# rev1.net
KiCad netlist of a schematic drawn in EAGLE
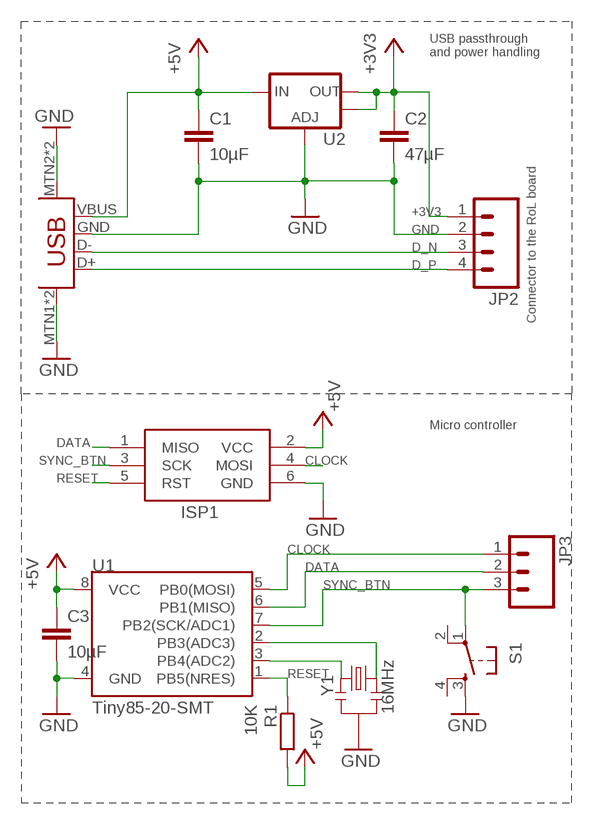
[diagram p0: schematic, sheet 1]

(export (version "E")
  (design (tool "Eeschema 10.0.6"))
  (components
    (comp (ref "C1")
      (value "10µF")
      (footprint "eagle-import:C3216")
      (libsource (lib "eagle-import") (part "C-EUC3216"))
    )
    (comp (ref "C2")
      (value "47µF")
      (footprint "eagle-import:C3216")
      (libsource (lib "eagle-import") (part "C-EUC3216"))
    )
    (comp (ref "C3")
      (value "10µF")
      (footprint "eagle-import:C3216")
      (libsource (lib "eagle-import") (part "C-EUC3216"))
    )
    (comp (ref "ISP1")
      (value "AVRISP-6")
      (footprint "eagle-import:AVRISP")
      (libsource (lib "eagle-import") (part "AVRISP-6"))
    )
    (comp (ref "JP1")
      (value "USBSMD")
      (footprint "eagle-import:USB-MINIB")
      (libsource (lib "eagle-import") (part "USBSMD"))
    )
    (comp (ref "JP2")
      (value "M04LOCK")
      (footprint "eagle-import:1X04_LOCK")
      (libsource (lib "eagle-import") (part "M04LOCK"))
    )
    (comp (ref "JP3")
      (value "M03LOCK")
      (footprint "eagle-import:1X03_LOCK")
      (libsource (lib "eagle-import") (part "M03LOCK"))
    )
    (comp (ref "R1")
      (value "10K")
      (footprint "eagle-import:R0603")
      (libsource (lib "eagle-import") (part "R-EU_R0603"))
    )
    (comp (ref "S1")
      (value "TAC_SWITCHPTH")
      (footprint "eagle-import:TACTILE-PTH")
      (libsource (lib "eagle-import") (part "TAC_SWITCHPTH"))
    )
    (comp (ref "U1")
      (value "Tiny85-20-SMT")
      (footprint "eagle-import:SO08-EIAJ")
      (libsource (lib "eagle-import") (part "ATTINY45TINY85-20-SMT"))
    )
    (comp (ref "U2")
      (value "V_REG_LM1117SOT223")
      (footprint "eagle-import:SOT223")
      (libsource (lib "eagle-import") (part "V_REG_LM1117SOT223"))
    )
    (comp (ref "Y1")
      (value "16MHz")
      (footprint "eagle-import:RESONATOR-SMD")
      (libsource (lib "eagle-import") (part "RESONATORSMD"))
    )
  )
  (nets
    (net (code "1") (name "+3V3") (class "Default")
      (node (ref "C2") (pin "1") (pinfunction "1_1") (pintype "passive"))
      (node (ref "JP2") (pin "1") (pinfunction "1_1") (pintype "passive"))
      (node (ref "U2") (pin "2") (pinfunction "OUT_2") (pintype "output"))
      (node (ref "U2") (pin "4") (pinfunction "OUT_4") (pintype "output"))
    )
    (net (code "2") (name "+5V") (class "Default")
      (node (ref "C1") (pin "1") (pinfunction "1_1") (pintype "passive"))
      (node (ref "C3") (pin "1") (pinfunction "1_1") (pintype "passive"))
      (node (ref "ISP1") (pin "2") (pinfunction "VCC_2") (pintype "power_in"))
      (node (ref "JP1") (pin "VBUS") (pinfunction "VBUS_VBUS") (pintype "bidirectional"))
      (node (ref "R1") (pin "2") (pinfunction "2_2") (pintype "passive"))
      (node (ref "U1") (pin "8") (pinfunction "VCC_8") (pintype "bidirectional"))
      (node (ref "U2") (pin "3") (pinfunction "IN_3") (pintype "input"))
    )
    (net (code "3") (name "/CLOCK") (class "Default")
      (node (ref "ISP1") (pin "4") (pinfunction "MOSI_4") (pintype "output"))
      (node (ref "JP3") (pin "1") (pinfunction "1_1") (pintype "passive"))
      (node (ref "U1") (pin "5") (pinfunction "PB0(MOSI)_5") (pintype "bidirectional"))
    )
    (net (code "4") (name "/DATA") (class "Default")
      (node (ref "ISP1") (pin "1") (pinfunction "MISO_1") (pintype "input"))
      (node (ref "JP3") (pin "2") (pinfunction "2_2") (pintype "passive"))
      (node (ref "U1") (pin "6") (pinfunction "PB1(MISO)_6") (pintype "bidirectional"))
    )
    (net (code "5") (name "/D_N") (class "Default")
      (node (ref "JP1") (pin "D-") (pinfunction "D-_D-") (pintype "bidirectional"))
      (node (ref "JP2") (pin "3") (pinfunction "3_3") (pintype "passive"))
    )
    (net (code "6") (name "/D_P") (class "Default")
      (node (ref "JP1") (pin "D+") (pinfunction "D+_D+") (pintype "bidirectional"))
      (node (ref "JP2") (pin "4") (pinfunction "4_4") (pintype "passive"))
    )
    (net (code "7") (name "/RESET") (class "Default")
      (node (ref "ISP1") (pin "5") (pinfunction "RST_5") (pintype "output"))
      (node (ref "R1") (pin "1") (pinfunction "1_1") (pintype "passive"))
      (node (ref "U1") (pin "1") (pinfunction "PB5(NRES)_1") (pintype "bidirectional"))
    )
    (net (code "8") (name "/SYNC_BTN") (class "Default")
      (node (ref "ISP1") (pin "3") (pinfunction "SCK_3") (pintype "output"))
      (node (ref "JP3") (pin "3") (pinfunction "3_3") (pintype "passive"))
      (node (ref "S1") (pin "1") (pinfunction "1_1") (pintype "passive"))
      (node (ref "U1") (pin "7") (pinfunction "PB2(SCK/ADC1)_7") (pintype "bidirectional"))
    )
    (net (code "9") (name "GND") (class "Default")
      (node (ref "C1") (pin "2") (pinfunction "2_2") (pintype "passive"))
      (node (ref "C2") (pin "2") (pinfunction "2_2") (pintype "passive"))
      (node (ref "C3") (pin "2") (pinfunction "2_2") (pintype "passive"))
      (node (ref "ISP1") (pin "6") (pinfunction "GND_6") (pintype "power_in"))
      (node (ref "JP1") (pin "GND") (pinfunction "GND_GND") (pintype "bidirectional"))
      (node (ref "JP1") (pin "MTN1") (pinfunction "MNT_MTN1") (pintype "bidirectional"))
      (node (ref "JP1") (pin "MTN2") (pinfunction "MNT2_MTN2") (pintype "bidirectional"))
      (node (ref "JP1") (pin "MTN3") (pinfunction "MNT2_MTN3") (pintype "bidirectional"))
      (node (ref "JP1") (pin "MTN4") (pinfunction "MNT_MTN4") (pintype "bidirectional"))
      (node (ref "JP2") (pin "2") (pinfunction "2_2") (pintype "passive"))
      (node (ref "S1") (pin "3") (pinfunction "3_3") (pintype "passive"))
      (node (ref "U1") (pin "4") (pinfunction "GND_4") (pintype "bidirectional"))
      (node (ref "U2") (pin "1") (pinfunction "ADJ_1") (pintype "input"))
      (node (ref "Y1") (pin "2") (pinfunction "2_2") (pintype "passive"))
    )
    (net (code "10") (name "Net-(U1-PB3(ADC3))") (class "Default")
      (node (ref "U1") (pin "2") (pinfunction "PB3(ADC3)_2") (pintype "bidirectional"))
      (node (ref "Y1") (pin "3") (pinfunction "3_3") (pintype "passive"))
    )
    (net (code "11") (name "Net-(U1-PB4(ADC2))") (class "Default")
      (node (ref "U1") (pin "3") (pinfunction "PB4(ADC2)_3") (pintype "bidirectional"))
      (node (ref "Y1") (pin "1") (pinfunction "1_1") (pintype "passive"))
    )
    (net (code "12") (name "unconnected-(S1-Pad2)") (class "Default")
      (node (ref "S1") (pin "2") (pinfunction "2_2") (pintype "passive"))
    )
    (net (code "13") (name "unconnected-(S1-Pad4)") (class "Default")
      (node (ref "S1") (pin "4") (pinfunction "4_4") (pintype "passive"))
    )
  )
)
